# eodrover.net
KiCad netlist of a schematic drawn in EAGLE
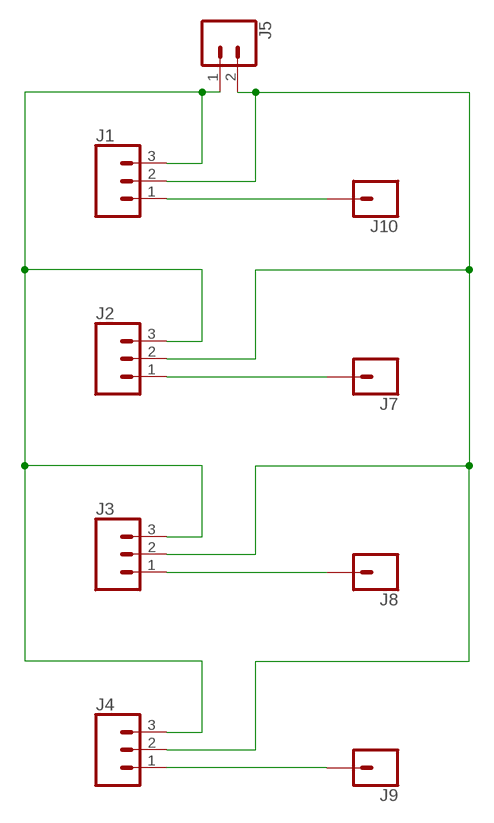
[diagram p0: schematic, sheet 1]

(export (version "E")
  (design (tool "Eeschema 10.0.6"))
  (components
    (comp (ref "J1")
      (value "CONN_03")
      (footprint "eagle-import:1X03")
      (libsource (lib "eagle-import") (part "CONN_03"))
    )
    (comp (ref "J2")
      (value "CONN_03")
      (footprint "eagle-import:1X03")
      (libsource (lib "eagle-import") (part "CONN_03"))
    )
    (comp (ref "J3")
      (value "CONN_03")
      (footprint "eagle-import:1X03")
      (libsource (lib "eagle-import") (part "CONN_03"))
    )
    (comp (ref "J4")
      (value "CONN_03")
      (footprint "eagle-import:1X03")
      (libsource (lib "eagle-import") (part "CONN_03"))
    )
    (comp (ref "J5")
      (value "CONN_02")
      (footprint "eagle-import:1X02")
      (libsource (lib "eagle-import") (part "CONN_02"))
    )
    (comp (ref "J7")
      (value "CONN_01")
      (footprint "eagle-import:1X01")
      (libsource (lib "eagle-import") (part "CONN_01"))
    )
    (comp (ref "J8")
      (value "CONN_01")
      (footprint "eagle-import:1X01")
      (libsource (lib "eagle-import") (part "CONN_01"))
    )
    (comp (ref "J9")
      (value "CONN_01")
      (footprint "eagle-import:1X01")
      (libsource (lib "eagle-import") (part "CONN_01"))
    )
    (comp (ref "J10")
      (value "CONN_01")
      (footprint "eagle-import:1X01")
      (libsource (lib "eagle-import") (part "CONN_01"))
    )
  )
  (nets
    (net (code "1") (name "Net-(J1-Pad1)") (class "Default")
      (node (ref "J1") (pin "1") (pinfunction "1_1") (pintype "passive"))
      (node (ref "J10") (pin "1") (pinfunction "1_1") (pintype "passive"))
    )
    (net (code "2") (name "Net-(J1-Pad2)") (class "Default")
      (node (ref "J1") (pin "2") (pinfunction "2_2") (pintype "passive"))
      (node (ref "J2") (pin "2") (pinfunction "2_2") (pintype "passive"))
      (node (ref "J3") (pin "2") (pinfunction "2_2") (pintype "passive"))
      (node (ref "J4") (pin "2") (pinfunction "2_2") (pintype "passive"))
      (node (ref "J5") (pin "2") (pinfunction "2_2") (pintype "passive"))
    )
    (net (code "3") (name "Net-(J1-Pad3)") (class "Default")
      (node (ref "J1") (pin "3") (pinfunction "3_3") (pintype "passive"))
      (node (ref "J2") (pin "3") (pinfunction "3_3") (pintype "passive"))
      (node (ref "J3") (pin "3") (pinfunction "3_3") (pintype "passive"))
      (node (ref "J4") (pin "3") (pinfunction "3_3") (pintype "passive"))
      (node (ref "J5") (pin "1") (pinfunction "1_1") (pintype "passive"))
    )
    (net (code "4") (name "Net-(J2-Pad1)") (class "Default")
      (node (ref "J2") (pin "1") (pinfunction "1_1") (pintype "passive"))
      (node (ref "J7") (pin "1") (pinfunction "1_1") (pintype "passive"))
    )
    (net (code "5") (name "Net-(J3-Pad1)") (class "Default")
      (node (ref "J3") (pin "1") (pinfunction "1_1") (pintype "passive"))
      (node (ref "J8") (pin "1") (pinfunction "1_1") (pintype "passive"))
    )
    (net (code "6") (name "Net-(J4-Pad1)") (class "Default")
      (node (ref "J4") (pin "1") (pinfunction "1_1") (pintype "passive"))
      (node (ref "J9") (pin "1") (pinfunction "1_1") (pintype "passive"))
    )
  )
)
